# tweeq-eMod_IR.net
KiCad netlist of a schematic drawn in EAGLE
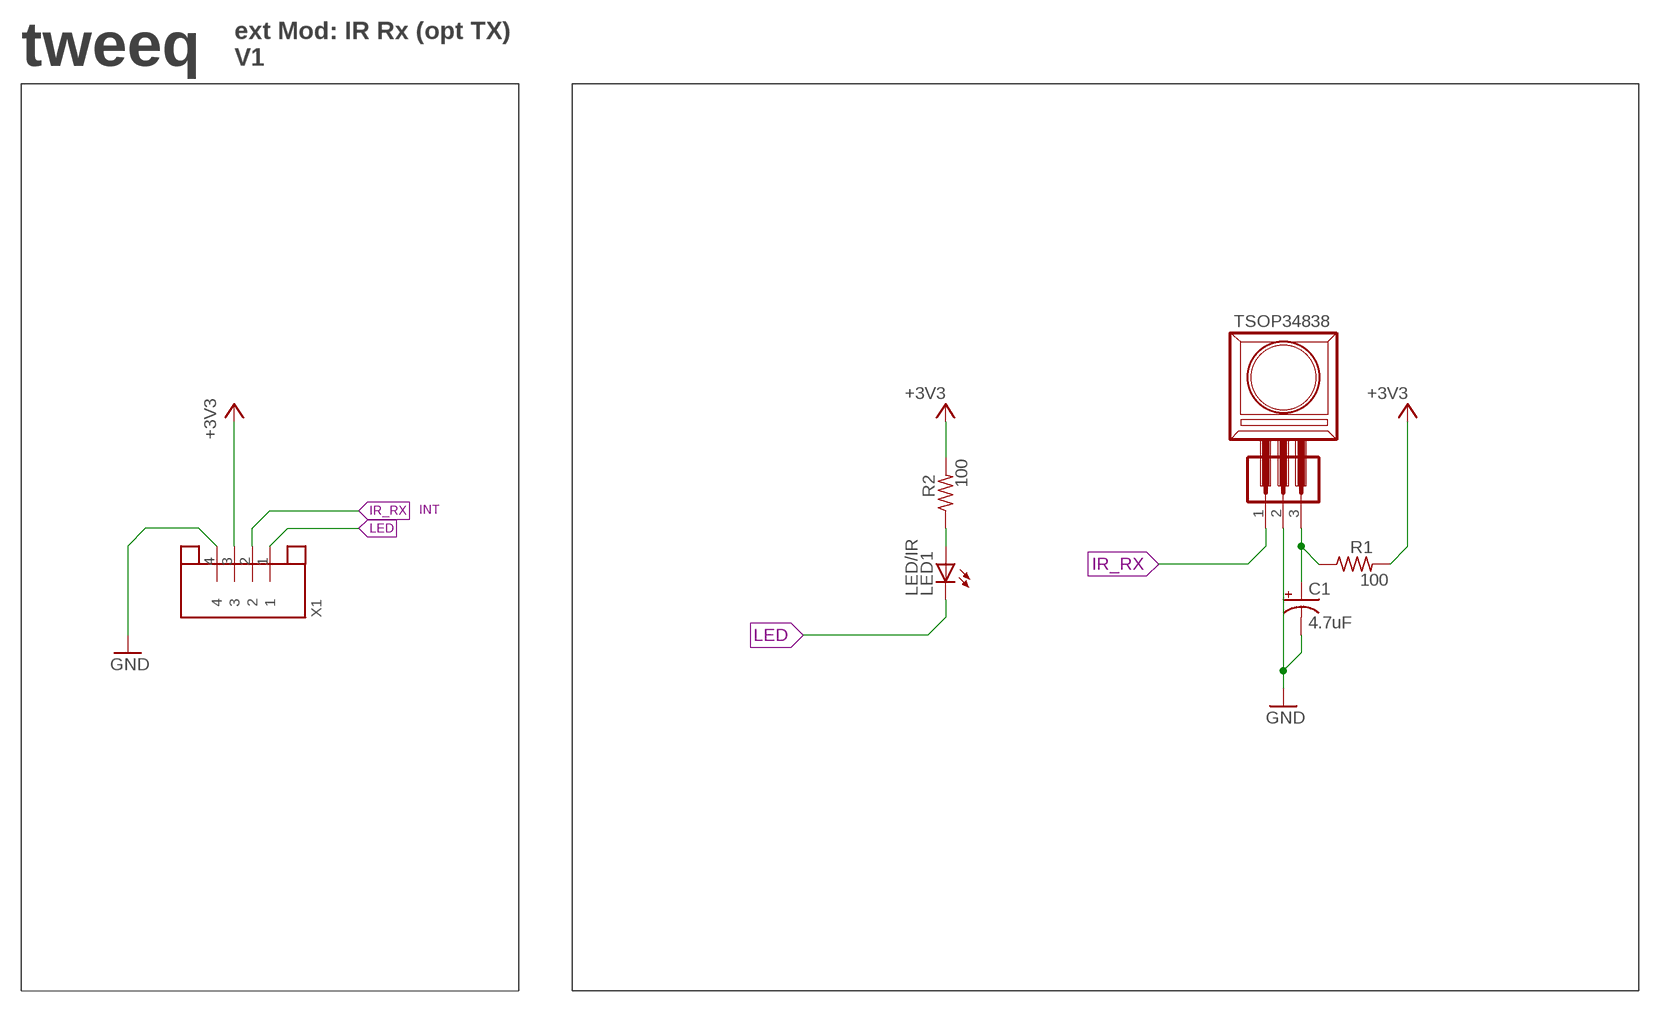
[diagram p0: schematic, sheet 1]

(export (version "E")
  (design (tool "Eeschema 10.0.6"))
  (components
    (comp (ref "C1")
      (value "4.7uF")
      (footprint "eagle-import:SMC_A")
      (libsource (lib "eagle-import") (part "CPOL-USSMCA"))
    )
    (comp (ref "LED1")
      (value "LED/IR")
      (footprint "eagle-import:CHIPLED_0805")
      (libsource (lib "eagle-import") (part "LEDCHIPLED_0805"))
    )
    (comp (ref "R1")
      (value "100")
      (footprint "eagle-import:R0603")
      (libsource (lib "eagle-import") (part "R-US_R0603"))
    )
    (comp (ref "R2")
      (value "100")
      (footprint "eagle-import:R0603")
      (libsource (lib "eagle-import") (part "R-US_R0603"))
    )
    (comp (ref "TSOP34838")
      (value "M03NS-SQ")
      (footprint "eagle-import:1X03-NS-SQ")
      (libsource (lib "eagle-import") (part "M03NS-SQ"))
    )
    (comp (ref "X1")
      (value "JST-4PINSH")
      (footprint "eagle-import:SH1.0-4PIN")
      (libsource (lib "eagle-import") (part "JST-4PINSH"))
    )
  )
  (nets
    (net (code "1") (name "+3V3") (class "Default")
      (node (ref "R1") (pin "2") (pinfunction "2_2") (pintype "passive"))
      (node (ref "R2") (pin "2") (pinfunction "2_2") (pintype "passive"))
      (node (ref "X1") (pin "3") (pinfunction "3_3") (pintype "bidirectional"))
    )
    (net (code "2") (name "GND") (class "Default")
      (node (ref "C1") (pin "-") (pinfunction "-_-") (pintype "passive"))
      (node (ref "TSOP34838") (pin "2") (pinfunction "2_2") (pintype "passive"))
      (node (ref "X1") (pin "4") (pinfunction "4_4") (pintype "bidirectional"))
    )
    (net (code "3") (name "IR_RX") (class "Default")
      (node (ref "TSOP34838") (pin "1") (pinfunction "1_1") (pintype "passive"))
      (node (ref "X1") (pin "2") (pinfunction "2_2") (pintype "bidirectional"))
    )
    (net (code "4") (name "LED") (class "Default")
      (node (ref "LED1") (pin "C") (pinfunction "C_C") (pintype "passive"))
      (node (ref "X1") (pin "1") (pinfunction "1_1") (pintype "bidirectional"))
    )
    (net (code "5") (name "Net-(C1-Pad+)") (class "Default")
      (node (ref "C1") (pin "+") (pinfunction "+_+") (pintype "passive"))
      (node (ref "R1") (pin "1") (pinfunction "1_1") (pintype "passive"))
      (node (ref "TSOP34838") (pin "3") (pinfunction "3_3") (pintype "passive"))
    )
    (net (code "6") (name "Net-(LED1-PadA)") (class "Default")
      (node (ref "LED1") (pin "A") (pinfunction "A_A") (pintype "passive"))
      (node (ref "R2") (pin "1") (pinfunction "1_1") (pintype "passive"))
    )
  )
)
